# Logic_Module_V3.net
KiCad netlist of a schematic drawn in EAGLE
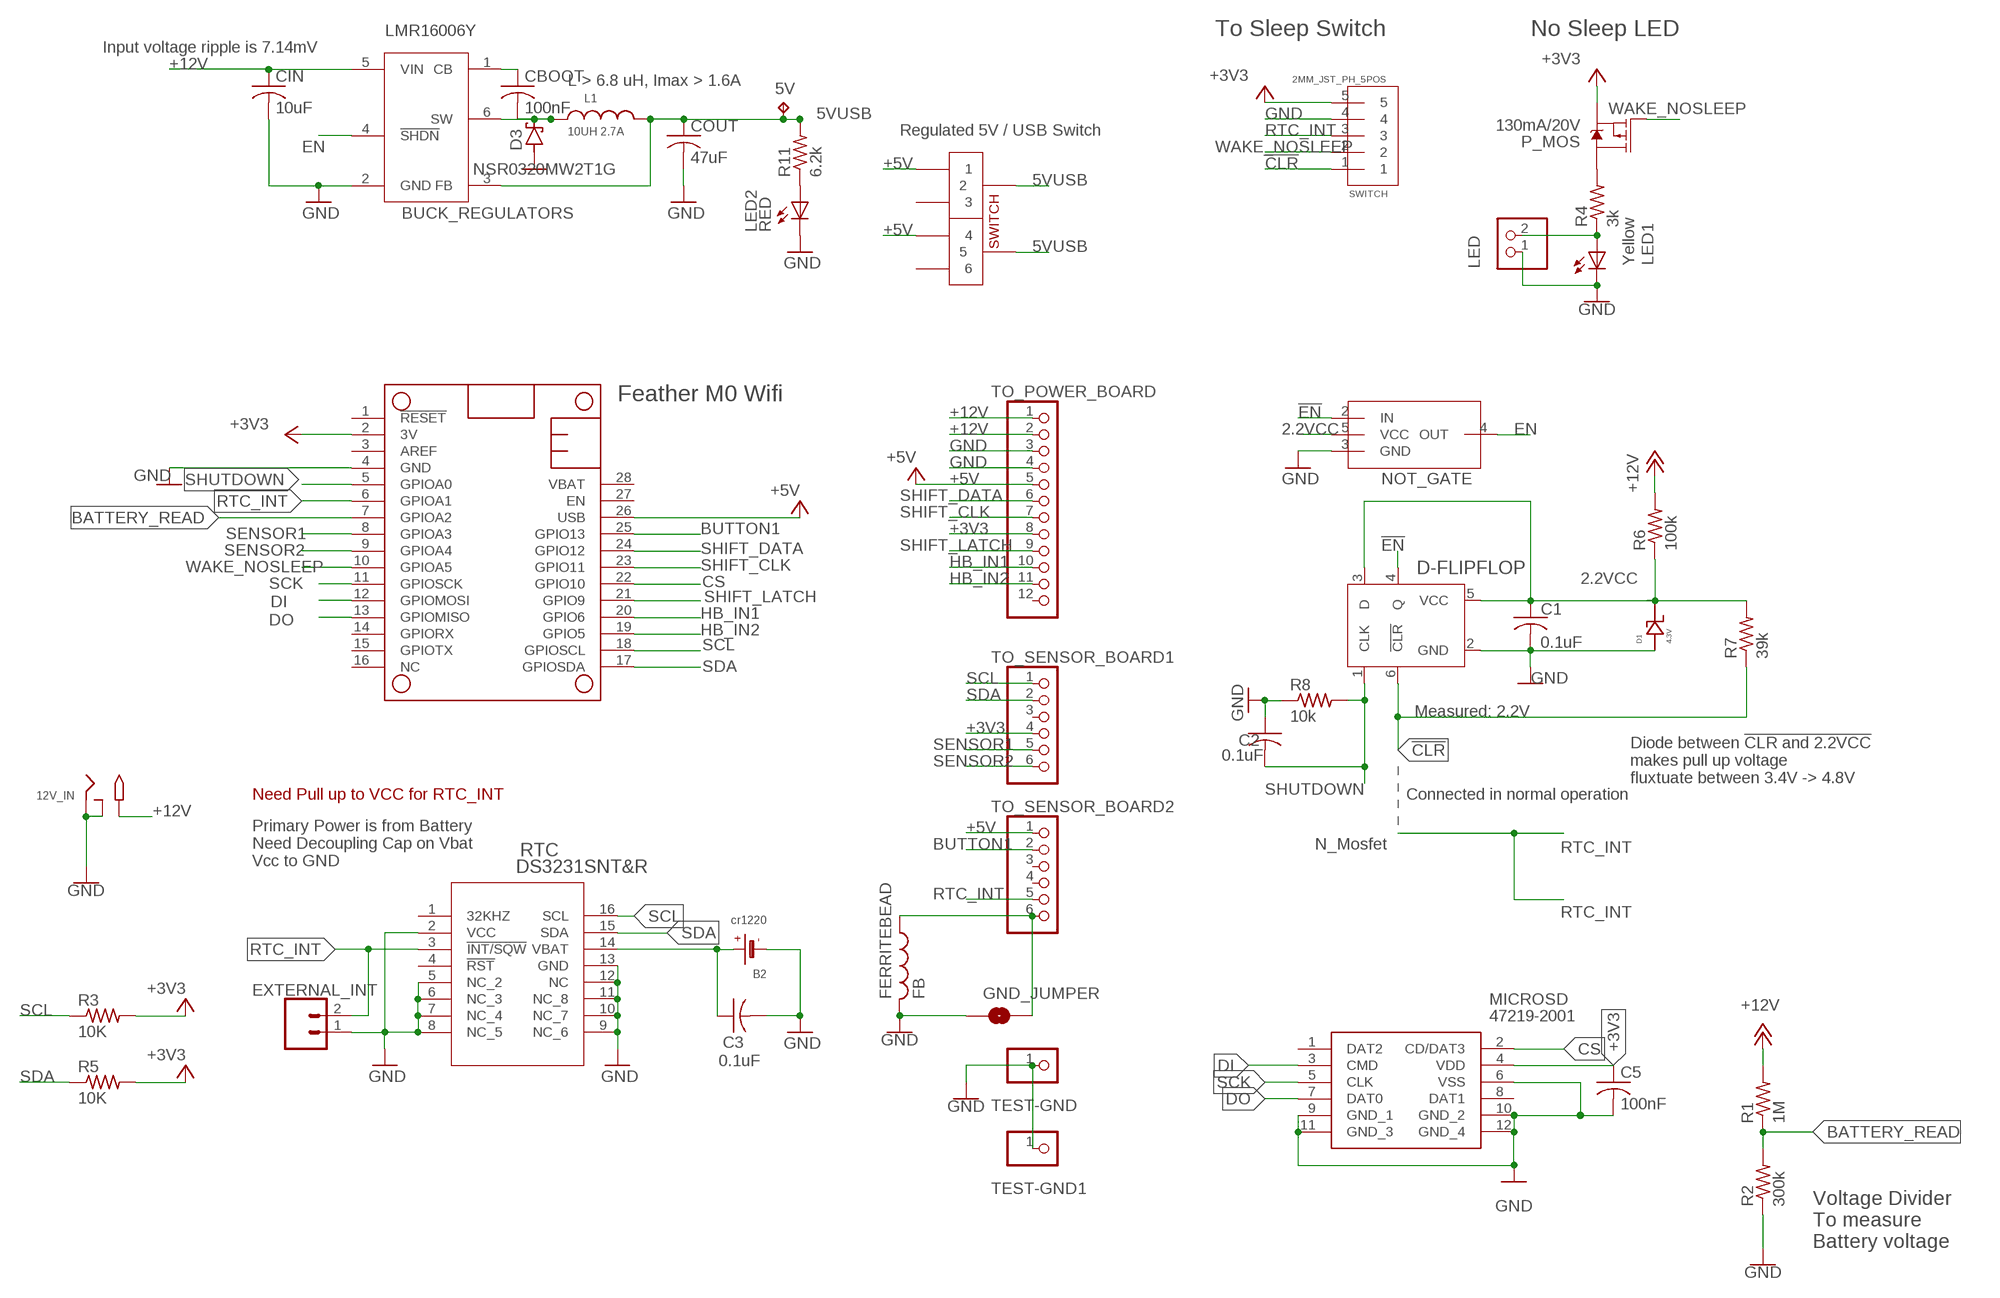
[diagram p0: schematic, sheet 1]

(export (version "E")
  (design (tool "Eeschema 10.0.6"))
  (components
    (comp (ref "5V")
      (value "TPTP16R")
      (footprint "eagle-import:TP16R")
      (libsource (lib "eagle-import") (part "TPTP16R"))
    )
    (comp (ref "12V_IN")
      (value "2.1MMJACKSMT")
      (footprint "eagle-import:DCJACK_2MM_SMT")
      (libsource (lib "eagle-import") (part "2.1MMJACKSMT"))
    )
    (comp (ref "B2")
      (value "cr1220")
      (footprint "eagle-import:CR1220-2")
      (libsource (lib "eagle-import") (part "BATTERYCR1220_2"))
    )
    (comp (ref "C1")
      (value "0.1uF")
      (footprint "eagle-import:C1206")
      (libsource (lib "eagle-import") (part "C-USC1206"))
    )
    (comp (ref "C2")
      (value "0.1uF")
      (footprint "eagle-import:C1206")
      (libsource (lib "eagle-import") (part "C-USC1206"))
    )
    (comp (ref "C3")
      (value "0.1uF")
      (footprint "eagle-import:C1206")
      (libsource (lib "eagle-import") (part "C-USC1206"))
    )
    (comp (ref "C5")
      (value "100nF")
      (footprint "eagle-import:C1206")
      (libsource (lib "eagle-import") (part "resistor_348_C-USC1206"))
    )
    (comp (ref "CBOOT")
      (value "100nF")
      (footprint "eagle-import:C1206")
      (libsource (lib "eagle-import") (part "rcl_334_C-USC1206"))
    )
    (comp (ref "CIN")
      (value "10uF")
      (footprint "eagle-import:C1206K")
      (libsource (lib "eagle-import") (part "rcl_334_C-USC1206K"))
    )
    (comp (ref "COUT")
      (value "47uF")
      (footprint "eagle-import:C1206")
      (libsource (lib "eagle-import") (part "rcl_334_C-USC1206"))
    )
    (comp (ref "D-FLIPFLOP")
      (value "SN74LVC1G175DBVR")
      (footprint "eagle-import:DBV6")
      (libsource (lib "eagle-import") (part "SN74LVC1G175DBVR"))
    )
    (comp (ref "D1")
      (value "4.3V")
      (footprint "eagle-import:DO-219AC")
      (libsource (lib "eagle-import") (part "ZENER-DO219"))
    )
    (comp (ref "D3")
      (value "NSR0320MW2T1G")
      (footprint "eagle-import:SOD323_ST")
      (libsource (lib "eagle-import") (part "BAT60J"))
    )
    (comp (ref "EXTERNAL_INT")
      (value "CONN_021X02_NO_SILK")
      (footprint "eagle-import:1X02_NO_SILK")
      (libsource (lib "eagle-import") (part "CONN_021X02_NO_SILK"))
    )
    (comp (ref "FERRITEBEAD")
      (value "FB")
      (footprint "eagle-import:FB")
      (libsource (lib "eagle-import") (part "FB"))
    )
    (comp (ref "GND_JUMPER")
      (value "JUMPER-SMT_2_NO_NO-SILK")
      (footprint "eagle-import:SMT-JUMPER_2_NO_NO-SILK")
      (libsource (lib "eagle-import") (part "JUMPER-SMT_2_NO_NO-SILK"))
    )
    (comp (ref "L1")
      (value "10UH 2.7A")
      (footprint "eagle-import:WE-MAPI_40XX")
      (libsource (lib "eagle-import") (part "WE-MAPI_4030_74438357100"))
    )
    (comp (ref "LED")
      (value "2.5MM_JST_UP_2POS")
      (footprint "eagle-import:JST_2POS_2.5MM_UP")
      (libsource (lib "eagle-import") (part "2.5MM_JST_UP_2POS"))
    )
    (comp (ref "LED1")
      (value "Yellow")
      (footprint "eagle-import:CHIPLED_0805")
      (libsource (lib "eagle-import") (part "LEDCHIPLED_0805"))
    )
    (comp (ref "LED2")
      (value "RED")
      (footprint "eagle-import:CHIPLED_0805")
      (libsource (lib "eagle-import") (part "LEDCHIPLED_0805"))
    )
    (comp (ref "MICROSD")
      (value "47219-2001")
      (footprint "eagle-import:472192001")
      (fields (field (name "MOUSER_PART_NUMBER") "538-47219-2001"))
      (libsource (lib "eagle-import") (part "47219-2001"))
    )
    (comp (ref "MS1")
      (value "FEATHERWING")
      (footprint "eagle-import:FEATHERWING")
      (libsource (lib "eagle-import") (part "FEATHERWING"))
    )
    (comp (ref "P_MOS")
      (value "130mA/20V")
      (footprint "eagle-import:SOT23-3")
      (libsource (lib "eagle-import") (part "MOSFET_PCH-IRLML2244"))
    )
    (comp (ref "R1")
      (value "1M")
      (footprint "eagle-import:R1206")
      (libsource (lib "eagle-import") (part "R-US_R1206"))
    )
    (comp (ref "R2")
      (value "300k")
      (footprint "eagle-import:R1206")
      (libsource (lib "eagle-import") (part "R-US_R1206"))
    )
    (comp (ref "R3")
      (value "10K")
      (footprint "eagle-import:R1206")
      (libsource (lib "eagle-import") (part "rcl_334_R-US_R1206"))
    )
    (comp (ref "R4")
      (value "3k")
      (footprint "eagle-import:R1206")
      (libsource (lib "eagle-import") (part "resistor_348_R-US_R1206"))
    )
    (comp (ref "R5")
      (value "10K")
      (footprint "eagle-import:R1206")
      (libsource (lib "eagle-import") (part "rcl_334_R-US_R1206"))
    )
    (comp (ref "R6")
      (value "100k")
      (footprint "eagle-import:R1206")
      (libsource (lib "eagle-import") (part "R-US_R1206"))
    )
    (comp (ref "R7")
      (value "39k")
      (footprint "eagle-import:R1206")
      (libsource (lib "eagle-import") (part "R-US_R1206"))
    )
    (comp (ref "R8")
      (value "10k")
      (footprint "eagle-import:R1206")
      (libsource (lib "eagle-import") (part "R-US_R1206"))
    )
    (comp (ref "R11")
      (value "6.2k")
      (footprint "eagle-import:RES_1206")
      (fields
        (field (name "DIGIKEY_PART_NUMBER") "WSLP-.05TR-ND")
        (field (name "MANUFACTURER") "Vishay Dale")
        (field (name "MPN") "WSLP1206R0500FEA")
        (field (name "CREATED_BY") "PCBLayout.com")
      )
      (libsource (lib "eagle-import") (part "WSLP1206R0500FEA"))
    )
    (comp (ref "RTC")
      (value "DS3231SNT&R")
      (footprint "eagle-import:21-0042B_16")
      (fields (field (name "MANUFACTURER_PART_NUMBER") "DS3231SN#T&R"))
      (libsource (lib "eagle-import") (part "DS3231SNT&R"))
    )
    (comp (ref "SWITCH")
      (value "2MM_JST_PH_5POS")
      (footprint "eagle-import:2MM_5POS_HEADER")
      (libsource (lib "eagle-import") (part "2MM_JST_PH_5POS"))
    )
    (comp (ref "TEST-GND")
      (value "PINHD-1X1")
      (footprint "eagle-import:1X01")
      (libsource (lib "eagle-import") (part "PINHD-1X1"))
    )
    (comp (ref "TEST-GND1")
      (value "PINHD-1X1")
      (footprint "eagle-import:1X01")
      (libsource (lib "eagle-import") (part "PINHD-1X1"))
    )
    (comp (ref "TO_POWER_BOARD")
      (value "PINHD-1X12")
      (footprint "eagle-import:1X12")
      (libsource (lib "eagle-import") (part "PINHD-1X12"))
    )
    (comp (ref "TO_SENSOR_BOARD1")
      (value "PINHD-1X6CB")
      (footprint "eagle-import:1X06-CLEANBIG")
      (libsource (lib "eagle-import") (part "PINHD-1X6CB"))
    )
    (comp (ref "TO_SENSOR_BOARD2")
      (value "PINHD-1X6CB")
      (footprint "eagle-import:1X06-CLEANBIG")
      (libsource (lib "eagle-import") (part "PINHD-1X6CB"))
    )
    (comp (ref "U$1")
      (value "2PDT_SWITCHJS-SMD")
      (footprint "eagle-import:JS-DPDT-SMD")
      (libsource (lib "eagle-import") (part "2PDT_SWITCHJS-SMD"))
    )
    (comp (ref "U$3")
      (value "NOT_GATE")
      (footprint "eagle-import:SOT753")
      (libsource (lib "eagle-import") (part "NOT_GATE"))
    )
    (comp (ref "VREG")
      (value "BUCK_REGULATORS")
      (footprint "eagle-import:SOT23-6")
      (libsource (lib "eagle-import") (part "BUCK_REGULATORS"))
    )
  )
  (nets
    (net (code "1") (name "+3V3") (class "Default")
      (node (ref "C5") (pin "1") (pinfunction "1_1") (pintype "passive"))
      (node (ref "MICROSD") (pin "4") (pinfunction "VDD_4") (pintype "bidirectional"))
      (node (ref "MS1") (pin "2") (pinfunction "3V_2") (pintype "power_in"))
      (node (ref "P_MOS") (pin "2") (pinfunction "S_2") (pintype "bidirectional"))
      (node (ref "R3") (pin "2") (pinfunction "2_2") (pintype "passive"))
      (node (ref "R5") (pin "2") (pinfunction "2_2") (pintype "passive"))
      (node (ref "SWITCH") (pin "5") (pinfunction "5_5") (pintype "bidirectional"))
      (node (ref "TO_POWER_BOARD") (pin "8") (pinfunction "8_8") (pintype "passive"))
      (node (ref "TO_SENSOR_BOARD1") (pin "4") (pinfunction "4_4") (pintype "passive"))
    )
    (net (code "2") (name "+5V") (class "Default")
      (node (ref "MS1") (pin "26") (pinfunction "USB_26") (pintype "power_in"))
      (node (ref "TO_POWER_BOARD") (pin "5") (pinfunction "5_5") (pintype "passive"))
      (node (ref "TO_SENSOR_BOARD2") (pin "1") (pinfunction "1_1") (pintype "passive"))
      (node (ref "U$1") (pin "P$1") (pinfunction "1_P$1") (pintype "bidirectional"))
      (node (ref "U$1") (pin "P$4") (pinfunction "4_P$4") (pintype "bidirectional"))
    )
    (net (code "3") (name "+12V") (class "Default")
      (node (ref "12V_IN") (pin "PWR2") (pinfunction "TIP_PWR2") (pintype "bidirectional"))
      (node (ref "CIN") (pin "1") (pinfunction "1_1") (pintype "passive"))
      (node (ref "R1") (pin "2") (pinfunction "2_2") (pintype "passive"))
      (node (ref "R6") (pin "2") (pinfunction "2_2") (pintype "passive"))
      (node (ref "TO_POWER_BOARD") (pin "1") (pinfunction "1_1") (pintype "passive"))
      (node (ref "TO_POWER_BOARD") (pin "2") (pinfunction "2_2") (pintype "passive"))
      (node (ref "VREG") (pin "5") (pinfunction "VIN_5") (pintype "bidirectional"))
    )
    (net (code "4") (name "/2.2VCC") (class "Default")
      (node (ref "C1") (pin "1") (pinfunction "1_1") (pintype "passive"))
      (node (ref "D-FLIPFLOP") (pin "3") (pinfunction "D_3") (pintype "input"))
      (node (ref "D-FLIPFLOP") (pin "5") (pinfunction "VCC_5") (pintype "power_in"))
      (node (ref "D1") (pin "FNT") (pinfunction "FNT_FNT") (pintype "bidirectional"))
      (node (ref "R6") (pin "1") (pinfunction "1_1") (pintype "passive"))
      (node (ref "R7") (pin "2") (pinfunction "2_2") (pintype "passive"))
      (node (ref "U$3") (pin "5") (pinfunction "VCC_5") (pintype "bidirectional"))
    )
    (net (code "5") (name "/5VUSB") (class "Default")
      (node (ref "5V") (pin "TP") (pinfunction "TP_TP") (pintype "input"))
      (node (ref "COUT") (pin "1") (pinfunction "1_1") (pintype "passive"))
      (node (ref "L1") (pin "2") (pinfunction "2_2") (pintype "passive"))
      (node (ref "R11") (pin "2") (pinfunction "2_2") (pintype "passive"))
      (node (ref "U$1") (pin "P$2") (pinfunction "2_P$2") (pintype "bidirectional"))
      (node (ref "U$1") (pin "P$5") (pinfunction "5_P$5") (pintype "bidirectional"))
      (node (ref "VREG") (pin "3") (pinfunction "FB_3") (pintype "bidirectional"))
    )
    (net (code "6") (name "/BUTTON1") (class "Default")
      (node (ref "MS1") (pin "25") (pinfunction "GPIO13_25") (pintype "bidirectional"))
      (node (ref "TO_SENSOR_BOARD2") (pin "2") (pinfunction "2_2") (pintype "passive"))
    )
    (net (code "7") (name "/EN") (class "Default")
      (node (ref "U$3") (pin "4") (pinfunction "OUT_4") (pintype "bidirectional"))
      (node (ref "VREG") (pin "4") (pinfunction "~{SHDN}_4") (pintype "bidirectional"))
    )
    (net (code "8") (name "/HB_IN1") (class "Default")
      (node (ref "MS1") (pin "20") (pinfunction "GPIO6_20") (pintype "bidirectional"))
      (node (ref "TO_POWER_BOARD") (pin "10") (pinfunction "10_10") (pintype "passive"))
    )
    (net (code "9") (name "/HB_IN2") (class "Default")
      (node (ref "MS1") (pin "19") (pinfunction "GPIO5_19") (pintype "bidirectional"))
      (node (ref "TO_POWER_BOARD") (pin "11") (pinfunction "11_11") (pintype "passive"))
    )
    (net (code "10") (name "/SENSOR1") (class "Default")
      (node (ref "MS1") (pin "8") (pinfunction "GPIOA3_8") (pintype "bidirectional"))
      (node (ref "TO_SENSOR_BOARD1") (pin "5") (pinfunction "5_5") (pintype "passive"))
    )
    (net (code "11") (name "/SENSOR2") (class "Default")
      (node (ref "MS1") (pin "9") (pinfunction "GPIOA4_9") (pintype "bidirectional"))
      (node (ref "TO_SENSOR_BOARD1") (pin "6") (pinfunction "6_6") (pintype "passive"))
    )
    (net (code "12") (name "/SHIFT_CLK") (class "Default")
      (node (ref "MS1") (pin "23") (pinfunction "GPIO11_23") (pintype "bidirectional"))
      (node (ref "TO_POWER_BOARD") (pin "7") (pinfunction "7_7") (pintype "passive"))
    )
    (net (code "13") (name "/SHIFT_DATA") (class "Default")
      (node (ref "MS1") (pin "24") (pinfunction "GPIO12_24") (pintype "bidirectional"))
      (node (ref "TO_POWER_BOARD") (pin "6") (pinfunction "6_6") (pintype "passive"))
    )
    (net (code "14") (name "/SHIFT_LATCH") (class "Default")
      (node (ref "MS1") (pin "21") (pinfunction "GPIO9_21") (pintype "bidirectional"))
      (node (ref "TO_POWER_BOARD") (pin "9") (pinfunction "9_9") (pintype "passive"))
    )
    (net (code "15") (name "/VBAT") (class "Default")
      (node (ref "MS1") (pin "28") (pinfunction "VBAT_28") (pintype "power_in"))
    )
    (net (code "16") (name "/WAKE_NOSLEEP") (class "Default")
      (node (ref "MS1") (pin "10") (pinfunction "GPIOA5_10") (pintype "bidirectional"))
      (node (ref "P_MOS") (pin "1") (pinfunction "G_1") (pintype "bidirectional"))
      (node (ref "SWITCH") (pin "2") (pinfunction "2_2") (pintype "bidirectional"))
    )
    (net (code "17") (name "/~{CLR}") (class "Default")
      (node (ref "D-FLIPFLOP") (pin "6") (pinfunction "~{CLR}_6") (pintype "input"))
      (node (ref "R7") (pin "1") (pinfunction "1_1") (pintype "passive"))
      (node (ref "SWITCH") (pin "1") (pinfunction "1_1") (pintype "bidirectional"))
    )
    (net (code "18") (name "/~{EN}") (class "Default")
      (node (ref "D-FLIPFLOP") (pin "4") (pinfunction "Q_4") (pintype "output"))
      (node (ref "U$3") (pin "2") (pinfunction "IN_2") (pintype "bidirectional"))
    )
    (net (code "19") (name "BATTERY_READ") (class "Default")
      (node (ref "MS1") (pin "7") (pinfunction "GPIOA2_7") (pintype "bidirectional"))
      (node (ref "R1") (pin "1") (pinfunction "1_1") (pintype "passive"))
      (node (ref "R2") (pin "2") (pinfunction "2_2") (pintype "passive"))
    )
    (net (code "20") (name "CS") (class "Default")
      (node (ref "MICROSD") (pin "2") (pinfunction "CD/DAT3_2") (pintype "bidirectional"))
      (node (ref "MS1") (pin "22") (pinfunction "GPIO10_22") (pintype "bidirectional"))
    )
    (net (code "21") (name "DI") (class "Default")
      (node (ref "MICROSD") (pin "3") (pinfunction "CMD_3") (pintype "bidirectional"))
      (node (ref "MS1") (pin "12") (pinfunction "GPIOMOSI_12") (pintype "bidirectional"))
    )
    (net (code "22") (name "DO") (class "Default")
      (node (ref "MICROSD") (pin "7") (pinfunction "DAT0_7") (pintype "bidirectional"))
      (node (ref "MS1") (pin "13") (pinfunction "GPIOMISO_13") (pintype "bidirectional"))
    )
    (net (code "23") (name "GND") (class "Default")
      (node (ref "12V_IN") (pin "GND") (pinfunction "RING_GND") (pintype "bidirectional"))
      (node (ref "12V_IN") (pin "GNDBREAK") (pinfunction "RING_SW_GNDBREAK") (pintype "bidirectional"))
      (node (ref "B2") (pin "-") (pinfunction "-_-") (pintype "passive"))
      (node (ref "C1") (pin "2") (pinfunction "2_2") (pintype "passive"))
      (node (ref "C2") (pin "1") (pinfunction "1_1") (pintype "passive"))
      (node (ref "C3") (pin "2") (pinfunction "2_2") (pintype "passive"))
      (node (ref "C5") (pin "2") (pinfunction "2_2") (pintype "passive"))
      (node (ref "CIN") (pin "2") (pinfunction "2_2") (pintype "passive"))
      (node (ref "COUT") (pin "2") (pinfunction "2_2") (pintype "passive"))
      (node (ref "D-FLIPFLOP") (pin "2") (pinfunction "GND_2") (pintype "power_in"))
      (node (ref "D1") (pin "BCK") (pinfunction "BCK_BCK") (pintype "bidirectional"))
      (node (ref "D3") (pin "A") (pinfunction "A_A") (pintype "passive"))
      (node (ref "EXTERNAL_INT") (pin "1") (pinfunction "1_1") (pintype "passive"))
      (node (ref "FERRITEBEAD") (pin "P$2") (pinfunction "2_P$2") (pintype "passive"))
      (node (ref "GND_JUMPER") (pin "1") (pinfunction "1_1") (pintype "passive"))
      (node (ref "LED") (pin "1") (pinfunction "1_1") (pintype "bidirectional"))
      (node (ref "LED1") (pin "C") (pinfunction "C_C") (pintype "passive"))
      (node (ref "LED2") (pin "C") (pinfunction "C_C") (pintype "passive"))
      (node (ref "MICROSD") (pin "10") (pinfunction "GND_2_10") (pintype "bidirectional"))
      (node (ref "MICROSD") (pin "11") (pinfunction "GND_3_11") (pintype "bidirectional"))
      (node (ref "MICROSD") (pin "12") (pinfunction "GND_4_12") (pintype "bidirectional"))
      (node (ref "MICROSD") (pin "6") (pinfunction "VSS_6") (pintype "bidirectional"))
      (node (ref "MICROSD") (pin "9") (pinfunction "GND_1_9") (pintype "bidirectional"))
      (node (ref "MS1") (pin "4") (pinfunction "GND_4") (pintype "power_in"))
      (node (ref "R2") (pin "1") (pinfunction "1_1") (pintype "passive"))
      (node (ref "R8") (pin "1") (pinfunction "1_1") (pintype "passive"))
      (node (ref "RTC") (pin "10") (pinfunction "NC_7_10") (pintype "passive"))
      (node (ref "RTC") (pin "11") (pinfunction "NC_8_11") (pintype "passive"))
      (node (ref "RTC") (pin "12") (pinfunction "NC_12") (pintype "passive"))
      (node (ref "RTC") (pin "13") (pinfunction "GND_13") (pintype "power_in"))
      (node (ref "RTC") (pin "2") (pinfunction "VCC_2") (pintype "power_in"))
      (node (ref "RTC") (pin "5") (pinfunction "NC_2_5") (pintype "passive"))
      (node (ref "RTC") (pin "6") (pinfunction "NC_3_6") (pintype "passive"))
      (node (ref "RTC") (pin "7") (pinfunction "NC_4_7") (pintype "passive"))
      (node (ref "RTC") (pin "8") (pinfunction "NC_5_8") (pintype "passive"))
      (node (ref "RTC") (pin "9") (pinfunction "NC_6_9") (pintype "passive"))
      (node (ref "SWITCH") (pin "4") (pinfunction "4_4") (pintype "bidirectional"))
      (node (ref "TEST-GND") (pin "1") (pinfunction "1_1") (pintype "passive"))
      (node (ref "TEST-GND1") (pin "1") (pinfunction "1_1") (pintype "passive"))
      (node (ref "TO_POWER_BOARD") (pin "3") (pinfunction "3_3") (pintype "passive"))
      (node (ref "TO_POWER_BOARD") (pin "4") (pinfunction "4_4") (pintype "passive"))
      (node (ref "U$3") (pin "3") (pinfunction "GND_3") (pintype "bidirectional"))
      (node (ref "VREG") (pin "2") (pinfunction "GND_2") (pintype "bidirectional"))
    )
    (net (code "24") (name "Net-(FERRITEBEAD-1)") (class "Default")
      (node (ref "FERRITEBEAD") (pin "P$1") (pinfunction "1_P$1") (pintype "passive"))
      (node (ref "GND_JUMPER") (pin "2") (pinfunction "2_2") (pintype "passive"))
      (node (ref "TO_SENSOR_BOARD2") (pin "6") (pinfunction "6_6") (pintype "passive"))
    )
    (net (code "25") (name "Net-(LED-Pad2)") (class "Default")
      (node (ref "LED") (pin "2") (pinfunction "2_2") (pintype "bidirectional"))
      (node (ref "LED1") (pin "A") (pinfunction "A_A") (pintype "passive"))
      (node (ref "R4") (pin "1") (pinfunction "1_1") (pintype "passive"))
    )
    (net (code "26") (name "Net-(LED2-PadA)") (class "Default")
      (node (ref "LED2") (pin "A") (pinfunction "A_A") (pintype "passive"))
      (node (ref "R11") (pin "1") (pinfunction "1_1") (pintype "passive"))
    )
    (net (code "27") (name "Net-(P_MOS-D)") (class "Default")
      (node (ref "P_MOS") (pin "3") (pinfunction "D_3") (pintype "bidirectional"))
      (node (ref "R4") (pin "2") (pinfunction "2_2") (pintype "passive"))
    )
    (net (code "28") (name "Net-(RTC-VBAT)") (class "Default")
      (node (ref "B2") (pin "+") (pinfunction "+_+") (pintype "passive"))
      (node (ref "C3") (pin "1") (pinfunction "1_1") (pintype "passive"))
      (node (ref "RTC") (pin "14") (pinfunction "VBAT_14") (pintype "power_in"))
    )
    (net (code "29") (name "Net-(VREG-CB)") (class "Default")
      (node (ref "CBOOT") (pin "1") (pinfunction "1_1") (pintype "passive"))
      (node (ref "VREG") (pin "1") (pinfunction "CB_1") (pintype "bidirectional"))
    )
    (net (code "30") (name "Net-(VREG-SW)") (class "Default")
      (node (ref "CBOOT") (pin "2") (pinfunction "2_2") (pintype "passive"))
      (node (ref "D3") (pin "C") (pinfunction "C_C") (pintype "passive"))
      (node (ref "L1") (pin "1") (pinfunction "1_1") (pintype "passive"))
      (node (ref "VREG") (pin "6") (pinfunction "SW_6") (pintype "bidirectional"))
    )
    (net (code "31") (name "RTC_INT") (class "Default")
      (node (ref "EXTERNAL_INT") (pin "2") (pinfunction "2_2") (pintype "passive"))
      (node (ref "MS1") (pin "6") (pinfunction "GPIOA1_6") (pintype "bidirectional"))
      (node (ref "RTC") (pin "3") (pinfunction "~{INT/SQW}_3") (pintype "passive"))
      (node (ref "SWITCH") (pin "3") (pinfunction "3_3") (pintype "bidirectional"))
      (node (ref "TO_SENSOR_BOARD2") (pin "5") (pinfunction "5_5") (pintype "passive"))
    )
    (net (code "32") (name "SCK") (class "Default")
      (node (ref "MICROSD") (pin "5") (pinfunction "CLK_5") (pintype "bidirectional"))
      (node (ref "MS1") (pin "11") (pinfunction "GPIOSCK_11") (pintype "bidirectional"))
    )
    (net (code "33") (name "SCL") (class "Default")
      (node (ref "MS1") (pin "18") (pinfunction "GPIOSCL_18") (pintype "bidirectional"))
      (node (ref "R3") (pin "1") (pinfunction "1_1") (pintype "passive"))
      (node (ref "RTC") (pin "16") (pinfunction "SCL_16") (pintype "passive"))
      (node (ref "TO_SENSOR_BOARD1") (pin "1") (pinfunction "1_1") (pintype "passive"))
    )
    (net (code "34") (name "SDA") (class "Default")
      (node (ref "MS1") (pin "17") (pinfunction "GPIOSDA_17") (pintype "bidirectional"))
      (node (ref "R5") (pin "1") (pinfunction "1_1") (pintype "passive"))
      (node (ref "RTC") (pin "15") (pinfunction "SDA_15") (pintype "passive"))
      (node (ref "TO_SENSOR_BOARD1") (pin "2") (pinfunction "2_2") (pintype "passive"))
    )
    (net (code "35") (name "SHUTDOWN") (class "Default")
      (node (ref "C2") (pin "2") (pinfunction "2_2") (pintype "passive"))
      (node (ref "D-FLIPFLOP") (pin "1") (pinfunction "CLK_1") (pintype "input"))
      (node (ref "MS1") (pin "5") (pinfunction "GPIOA0_5") (pintype "bidirectional"))
      (node (ref "R8") (pin "2") (pinfunction "2_2") (pintype "passive"))
    )
    (net (code "36") (name "unconnected-(MICROSD-DAT1-Pad8)") (class "Default")
      (node (ref "MICROSD") (pin "8") (pinfunction "DAT1_8") (pintype "bidirectional"))
    )
    (net (code "37") (name "unconnected-(MICROSD-DAT2-Pad1)") (class "Default")
      (node (ref "MICROSD") (pin "1") (pinfunction "DAT2_1") (pintype "bidirectional"))
    )
    (net (code "38") (name "unconnected-(MS1-AREF-Pad3)") (class "Default")
      (node (ref "MS1") (pin "3") (pinfunction "AREF_3") (pintype "passive"))
    )
    (net (code "39") (name "unconnected-(MS1-EN-Pad27)") (class "Default")
      (node (ref "MS1") (pin "27") (pinfunction "EN_27") (pintype "passive"))
    )
    (net (code "40") (name "unconnected-(MS1-GPIORX-Pad14)") (class "Default")
      (node (ref "MS1") (pin "14") (pinfunction "GPIORX_14") (pintype "bidirectional"))
    )
    (net (code "41") (name "unconnected-(MS1-GPIOTX-Pad15)") (class "Default")
      (node (ref "MS1") (pin "15") (pinfunction "GPIOTX_15") (pintype "bidirectional"))
    )
    (net (code "42") (name "unconnected-(MS1-NC-Pad16)") (class "Default")
      (node (ref "MS1") (pin "16") (pinfunction "NC_16") (pintype "passive"))
    )
    (net (code "43") (name "unconnected-(MS1-~{RESET}-Pad1)") (class "Default")
      (node (ref "MS1") (pin "1") (pinfunction "~{RESET}_1") (pintype "input"))
    )
    (net (code "44") (name "unconnected-(RTC-32KHZ-Pad1)") (class "Default")
      (node (ref "RTC") (pin "1") (pinfunction "32KHZ_1") (pintype "passive"))
    )
    (net (code "45") (name "unconnected-(RTC-~{RST}-Pad4)") (class "Default")
      (node (ref "RTC") (pin "4") (pinfunction "~{RST}_4") (pintype "passive"))
    )
    (net (code "46") (name "unconnected-(TO_POWER_BOARD-Pad12)") (class "Default")
      (node (ref "TO_POWER_BOARD") (pin "12") (pinfunction "12_12") (pintype "passive"))
    )
    (net (code "47") (name "unconnected-(TO_SENSOR_BOARD1-Pad3)") (class "Default")
      (node (ref "TO_SENSOR_BOARD1") (pin "3") (pinfunction "3_3") (pintype "passive"))
    )
    (net (code "48") (name "unconnected-(TO_SENSOR_BOARD2-Pad3)") (class "Default")
      (node (ref "TO_SENSOR_BOARD2") (pin "3") (pinfunction "3_3") (pintype "passive"))
    )
    (net (code "49") (name "unconnected-(TO_SENSOR_BOARD2-Pad4)") (class "Default")
      (node (ref "TO_SENSOR_BOARD2") (pin "4") (pinfunction "4_4") (pintype "passive"))
    )
    (net (code "50") (name "unconnected-(U$1-3-PadP$3)") (class "Default")
      (node (ref "U$1") (pin "P$3") (pinfunction "3_P$3") (pintype "bidirectional"))
    )
    (net (code "51") (name "unconnected-(U$1-6-PadP$6)") (class "Default")
      (node (ref "U$1") (pin "P$6") (pinfunction "6_P$6") (pintype "bidirectional"))
    )
  )
)
